# Sensor.net
KiCad netlist of a schematic drawn in Altium Designer
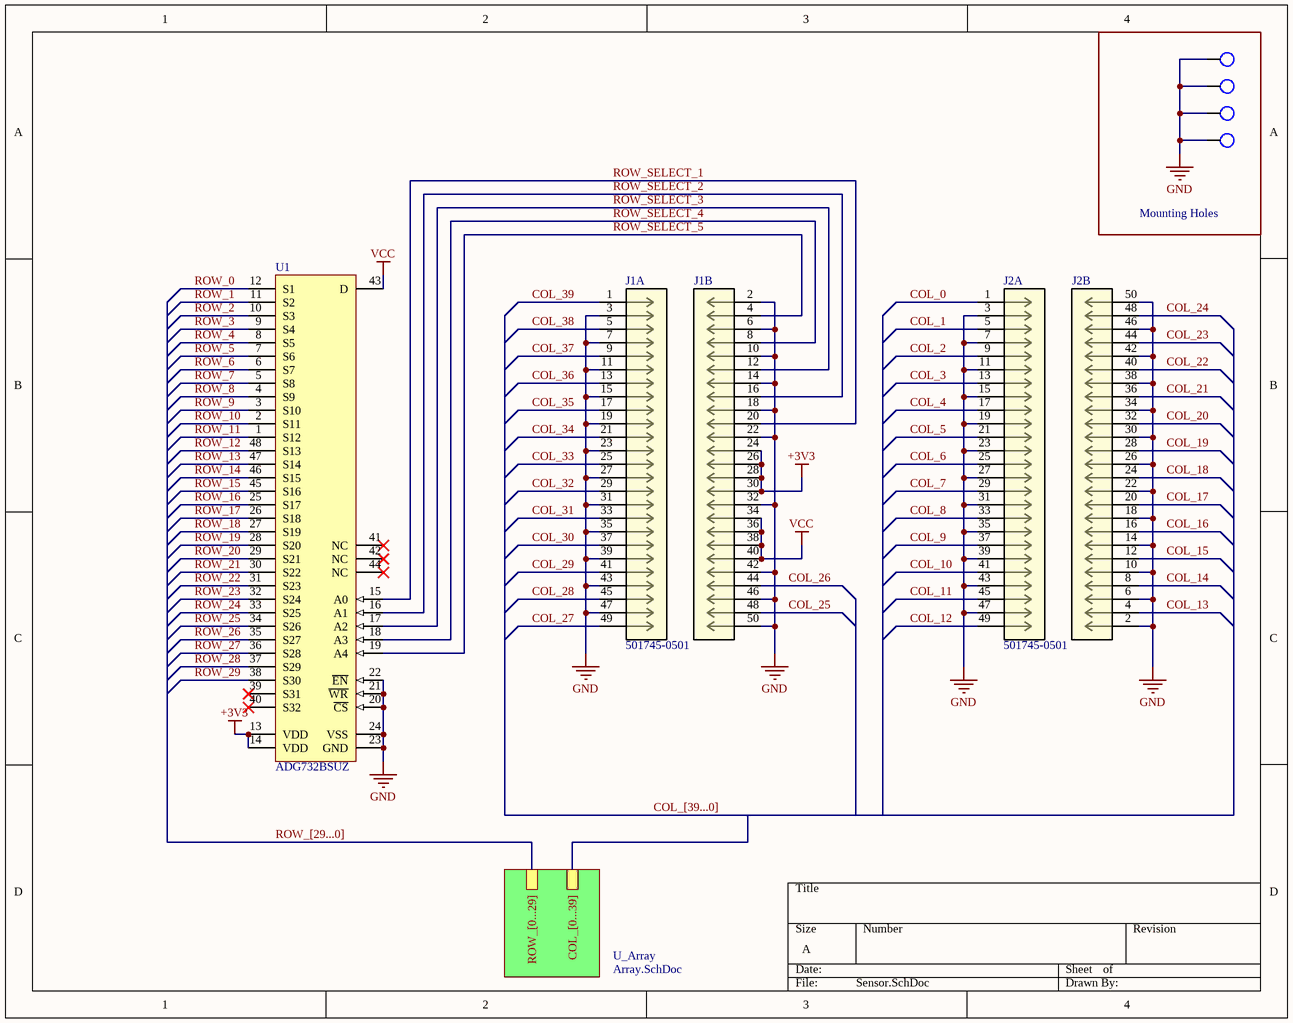
[diagram p0: Sensor.SchDoc]

(export (version "E")
  (design (tool "Eeschema 10.0.6"))
  (components
    (comp (ref "J1")
      (value "501745-0501")
      (footprint "501745-0501")
      (fields (field (name "MANUFACTURER") "Molex"))
      (libsource (lib "NeoObscura") (part "501745-0501"))
    )
    (comp (ref "J2")
      (value "501745-0501")
      (footprint "501745-0501")
      (fields (field (name "MANUFACTURER") "Molex"))
      (libsource (lib "NeoObscura") (part "501745-0501"))
    )
    (comp (ref "MP1")
      (value "M3 MOUNTING HOLE")
      (footprint "M3 MOUNTING HOLE")
      (libsource (lib "NeoObscura") (part "M3 MOUNTING HOLE"))
    )
    (comp (ref "MP2")
      (value "M3 MOUNTING HOLE")
      (footprint "M3 MOUNTING HOLE")
      (libsource (lib "NeoObscura") (part "M3 MOUNTING HOLE"))
    )
    (comp (ref "MP3")
      (value "M3 MOUNTING HOLE")
      (footprint "M3 MOUNTING HOLE")
      (libsource (lib "NeoObscura") (part "M3 MOUNTING HOLE"))
    )
    (comp (ref "MP4")
      (value "M3 MOUNTING HOLE")
      (footprint "M3 MOUNTING HOLE")
      (libsource (lib "NeoObscura") (part "M3 MOUNTING HOLE"))
    )
    (comp (ref "U1")
      (value "ADG732BSUZ")
      (footprint "ADI-SU-48_M")
      (fields (field (name "MANUFACTURER") "Analog Devices"))
      (libsource (lib "Altium Content Vault") (part "ADI-ADG732-SU-48"))
    )
  )
  (nets
    (net (code "3") (name "+3V3") (class "Default")
      (node (ref "J1") (pin "24") (pinfunction "24_24") (pintype "passive"))
      (node (ref "J1") (pin "26") (pinfunction "26_26") (pintype "passive"))
      (node (ref "J1") (pin "28") (pinfunction "28_28") (pintype "passive"))
      (node (ref "J1") (pin "30") (pinfunction "30_30") (pintype "passive"))
      (node (ref "U1") (pin "13") (pinfunction "VDD_13") (pintype "power_in"))
      (node (ref "U1") (pin "14") (pinfunction "VDD_14") (pintype "power_in"))
    )
    (net (code "4") (name "/COL_0") (class "Default")
      (node (ref "J2") (pin "1") (pinfunction "1_1") (pintype "passive"))
    )
    (net (code "5") (name "/COL_1") (class "Default")
      (node (ref "J2") (pin "5") (pinfunction "5_5") (pintype "passive"))
    )
    (net (code "6") (name "/COL_2") (class "Default")
      (node (ref "J2") (pin "9") (pinfunction "9_9") (pintype "passive"))
    )
    (net (code "7") (name "/COL_3") (class "Default")
      (node (ref "J2") (pin "13") (pinfunction "13_13") (pintype "passive"))
    )
    (net (code "8") (name "/COL_4") (class "Default")
      (node (ref "J2") (pin "17") (pinfunction "17_17") (pintype "passive"))
    )
    (net (code "9") (name "/COL_5") (class "Default")
      (node (ref "J2") (pin "21") (pinfunction "21_21") (pintype "passive"))
    )
    (net (code "10") (name "/COL_6") (class "Default")
      (node (ref "J2") (pin "25") (pinfunction "25_25") (pintype "passive"))
    )
    (net (code "11") (name "/COL_7") (class "Default")
      (node (ref "J2") (pin "29") (pinfunction "29_29") (pintype "passive"))
    )
    (net (code "12") (name "/COL_8") (class "Default")
      (node (ref "J2") (pin "33") (pinfunction "33_33") (pintype "passive"))
    )
    (net (code "13") (name "/COL_9") (class "Default")
      (node (ref "J2") (pin "37") (pinfunction "37_37") (pintype "passive"))
    )
    (net (code "14") (name "/COL_10") (class "Default")
      (node (ref "J2") (pin "41") (pinfunction "41_41") (pintype "passive"))
    )
    (net (code "15") (name "/COL_11") (class "Default")
      (node (ref "J2") (pin "45") (pinfunction "45_45") (pintype "passive"))
    )
    (net (code "16") (name "/COL_12") (class "Default")
      (node (ref "J2") (pin "49") (pinfunction "49_49") (pintype "passive"))
    )
    (net (code "17") (name "/COL_13") (class "Default")
      (node (ref "J2") (pin "4") (pinfunction "4_4") (pintype "passive"))
    )
    (net (code "18") (name "/COL_14") (class "Default")
      (node (ref "J2") (pin "8") (pinfunction "8_8") (pintype "passive"))
    )
    (net (code "19") (name "/COL_15") (class "Default")
      (node (ref "J2") (pin "12") (pinfunction "12_12") (pintype "passive"))
    )
    (net (code "20") (name "/COL_16") (class "Default")
      (node (ref "J2") (pin "16") (pinfunction "16_16") (pintype "passive"))
    )
    (net (code "21") (name "/COL_17") (class "Default")
      (node (ref "J2") (pin "20") (pinfunction "20_20") (pintype "passive"))
    )
    (net (code "22") (name "/COL_18") (class "Default")
      (node (ref "J2") (pin "24") (pinfunction "24_24") (pintype "passive"))
    )
    (net (code "23") (name "/COL_19") (class "Default")
      (node (ref "J2") (pin "28") (pinfunction "28_28") (pintype "passive"))
    )
    (net (code "24") (name "/COL_20") (class "Default")
      (node (ref "J2") (pin "32") (pinfunction "32_32") (pintype "passive"))
    )
    (net (code "25") (name "/COL_21") (class "Default")
      (node (ref "J2") (pin "36") (pinfunction "36_36") (pintype "passive"))
    )
    (net (code "26") (name "/COL_22") (class "Default")
      (node (ref "J2") (pin "40") (pinfunction "40_40") (pintype "passive"))
    )
    (net (code "27") (name "/COL_23") (class "Default")
      (node (ref "J2") (pin "44") (pinfunction "44_44") (pintype "passive"))
    )
    (net (code "28") (name "/COL_24") (class "Default")
      (node (ref "J2") (pin "48") (pinfunction "48_48") (pintype "passive"))
    )
    (net (code "29") (name "/COL_25") (class "Default")
      (node (ref "J1") (pin "48") (pinfunction "48_48") (pintype "passive"))
    )
    (net (code "30") (name "/COL_26") (class "Default")
      (node (ref "J1") (pin "44") (pinfunction "44_44") (pintype "passive"))
    )
    (net (code "31") (name "/COL_27") (class "Default")
      (node (ref "J1") (pin "49") (pinfunction "49_49") (pintype "passive"))
    )
    (net (code "32") (name "/COL_28") (class "Default")
      (node (ref "J1") (pin "45") (pinfunction "45_45") (pintype "passive"))
    )
    (net (code "33") (name "/COL_29") (class "Default")
      (node (ref "J1") (pin "41") (pinfunction "41_41") (pintype "passive"))
    )
    (net (code "34") (name "/COL_30") (class "Default")
      (node (ref "J1") (pin "37") (pinfunction "37_37") (pintype "passive"))
    )
    (net (code "35") (name "/COL_31") (class "Default")
      (node (ref "J1") (pin "33") (pinfunction "33_33") (pintype "passive"))
    )
    (net (code "36") (name "/COL_32") (class "Default")
      (node (ref "J1") (pin "29") (pinfunction "29_29") (pintype "passive"))
    )
    (net (code "37") (name "/COL_33") (class "Default")
      (node (ref "J1") (pin "25") (pinfunction "25_25") (pintype "passive"))
    )
    (net (code "38") (name "/COL_34") (class "Default")
      (node (ref "J1") (pin "21") (pinfunction "21_21") (pintype "passive"))
    )
    (net (code "39") (name "/COL_35") (class "Default")
      (node (ref "J1") (pin "17") (pinfunction "17_17") (pintype "passive"))
    )
    (net (code "40") (name "/COL_36") (class "Default")
      (node (ref "J1") (pin "13") (pinfunction "13_13") (pintype "passive"))
    )
    (net (code "41") (name "/COL_37") (class "Default")
      (node (ref "J1") (pin "9") (pinfunction "9_9") (pintype "passive"))
    )
    (net (code "42") (name "/COL_38") (class "Default")
      (node (ref "J1") (pin "5") (pinfunction "5_5") (pintype "passive"))
    )
    (net (code "43") (name "/COL_39") (class "Default")
      (node (ref "J1") (pin "1") (pinfunction "1_1") (pintype "passive"))
    )
    (net (code "44") (name "/ROW_0") (class "Default")
      (node (ref "U1") (pin "12") (pinfunction "S1_12") (pintype "passive"))
    )
    (net (code "45") (name "/ROW_1") (class "Default")
      (node (ref "U1") (pin "11") (pinfunction "S2_11") (pintype "passive"))
    )
    (net (code "46") (name "/ROW_2") (class "Default")
      (node (ref "U1") (pin "10") (pinfunction "S3_10") (pintype "passive"))
    )
    (net (code "47") (name "/ROW_3") (class "Default")
      (node (ref "U1") (pin "9") (pinfunction "S4_9") (pintype "passive"))
    )
    (net (code "48") (name "/ROW_4") (class "Default")
      (node (ref "U1") (pin "8") (pinfunction "S5_8") (pintype "passive"))
    )
    (net (code "49") (name "/ROW_5") (class "Default")
      (node (ref "U1") (pin "7") (pinfunction "S6_7") (pintype "passive"))
    )
    (net (code "50") (name "/ROW_6") (class "Default")
      (node (ref "U1") (pin "6") (pinfunction "S7_6") (pintype "passive"))
    )
    (net (code "51") (name "/ROW_7") (class "Default")
      (node (ref "U1") (pin "5") (pinfunction "S8_5") (pintype "passive"))
    )
    (net (code "52") (name "/ROW_8") (class "Default")
      (node (ref "U1") (pin "4") (pinfunction "S9_4") (pintype "passive"))
    )
    (net (code "53") (name "/ROW_9") (class "Default")
      (node (ref "U1") (pin "3") (pinfunction "S10_3") (pintype "passive"))
    )
    (net (code "54") (name "/ROW_10") (class "Default")
      (node (ref "U1") (pin "2") (pinfunction "S11_2") (pintype "passive"))
    )
    (net (code "55") (name "/ROW_11") (class "Default")
      (node (ref "U1") (pin "1") (pinfunction "S12_1") (pintype "passive"))
    )
    (net (code "56") (name "/ROW_12") (class "Default")
      (node (ref "U1") (pin "48") (pinfunction "S13_48") (pintype "passive"))
    )
    (net (code "57") (name "/ROW_13") (class "Default")
      (node (ref "U1") (pin "47") (pinfunction "S14_47") (pintype "passive"))
    )
    (net (code "58") (name "/ROW_14") (class "Default")
      (node (ref "U1") (pin "46") (pinfunction "S15_46") (pintype "passive"))
    )
    (net (code "59") (name "/ROW_15") (class "Default")
      (node (ref "U1") (pin "45") (pinfunction "S16_45") (pintype "passive"))
    )
    (net (code "60") (name "/ROW_16") (class "Default")
      (node (ref "U1") (pin "25") (pinfunction "S17_25") (pintype "passive"))
    )
    (net (code "61") (name "/ROW_17") (class "Default")
      (node (ref "U1") (pin "26") (pinfunction "S18_26") (pintype "passive"))
    )
    (net (code "62") (name "/ROW_18") (class "Default")
      (node (ref "U1") (pin "27") (pinfunction "S19_27") (pintype "passive"))
    )
    (net (code "63") (name "/ROW_19") (class "Default")
      (node (ref "U1") (pin "28") (pinfunction "S20_28") (pintype "passive"))
    )
    (net (code "64") (name "/ROW_20") (class "Default")
      (node (ref "U1") (pin "29") (pinfunction "S21_29") (pintype "passive"))
    )
    (net (code "65") (name "/ROW_21") (class "Default")
      (node (ref "U1") (pin "30") (pinfunction "S22_30") (pintype "passive"))
    )
    (net (code "66") (name "/ROW_22") (class "Default")
      (node (ref "U1") (pin "31") (pinfunction "S23_31") (pintype "passive"))
    )
    (net (code "67") (name "/ROW_23") (class "Default")
      (node (ref "U1") (pin "32") (pinfunction "S24_32") (pintype "passive"))
    )
    (net (code "68") (name "/ROW_24") (class "Default")
      (node (ref "U1") (pin "33") (pinfunction "S25_33") (pintype "passive"))
    )
    (net (code "69") (name "/ROW_25") (class "Default")
      (node (ref "U1") (pin "34") (pinfunction "S26_34") (pintype "passive"))
    )
    (net (code "70") (name "/ROW_26") (class "Default")
      (node (ref "U1") (pin "35") (pinfunction "S27_35") (pintype "passive"))
    )
    (net (code "71") (name "/ROW_27") (class "Default")
      (node (ref "U1") (pin "36") (pinfunction "S28_36") (pintype "passive"))
    )
    (net (code "72") (name "/ROW_28") (class "Default")
      (node (ref "U1") (pin "37") (pinfunction "S29_37") (pintype "passive"))
    )
    (net (code "73") (name "/ROW_29") (class "Default")
      (node (ref "U1") (pin "38") (pinfunction "S30_38") (pintype "passive"))
    )
    (net (code "74") (name "/ROW_SELECT_1") (class "Default")
      (node (ref "J1") (pin "20") (pinfunction "20_20") (pintype "passive"))
      (node (ref "U1") (pin "15") (pinfunction "A0_15") (pintype "input"))
    )
    (net (code "75") (name "/ROW_SELECT_2") (class "Default")
      (node (ref "J1") (pin "16") (pinfunction "16_16") (pintype "passive"))
      (node (ref "U1") (pin "16") (pinfunction "A1_16") (pintype "input"))
    )
    (net (code "76") (name "/ROW_SELECT_3") (class "Default")
      (node (ref "J1") (pin "12") (pinfunction "12_12") (pintype "passive"))
      (node (ref "U1") (pin "17") (pinfunction "A2_17") (pintype "input"))
    )
    (net (code "77") (name "/ROW_SELECT_4") (class "Default")
      (node (ref "J1") (pin "8") (pinfunction "8_8") (pintype "passive"))
      (node (ref "U1") (pin "18") (pinfunction "A3_18") (pintype "input"))
    )
    (net (code "78") (name "/ROW_SELECT_5") (class "Default")
      (node (ref "J1") (pin "4") (pinfunction "4_4") (pintype "passive"))
      (node (ref "U1") (pin "19") (pinfunction "A4_19") (pintype "input"))
    )
    (net (code "81") (name "GND") (class "Default")
      (node (ref "J1") (pin "10") (pinfunction "10_10") (pintype "passive"))
      (node (ref "J1") (pin "11") (pinfunction "11_11") (pintype "passive"))
      (node (ref "J1") (pin "14") (pinfunction "14_14") (pintype "passive"))
      (node (ref "J1") (pin "15") (pinfunction "15_15") (pintype "passive"))
      (node (ref "J1") (pin "18") (pinfunction "18_18") (pintype "passive"))
      (node (ref "J1") (pin "19") (pinfunction "19_19") (pintype "passive"))
      (node (ref "J1") (pin "2") (pinfunction "2_2") (pintype "passive"))
      (node (ref "J1") (pin "22") (pinfunction "22_22") (pintype "passive"))
      (node (ref "J1") (pin "23") (pinfunction "23_23") (pintype "passive"))
      (node (ref "J1") (pin "27") (pinfunction "27_27") (pintype "passive"))
      (node (ref "J1") (pin "3") (pinfunction "3_3") (pintype "passive"))
      (node (ref "J1") (pin "31") (pinfunction "31_31") (pintype "passive"))
      (node (ref "J1") (pin "32") (pinfunction "32_32") (pintype "passive"))
      (node (ref "J1") (pin "35") (pinfunction "35_35") (pintype "passive"))
      (node (ref "J1") (pin "39") (pinfunction "39_39") (pintype "passive"))
      (node (ref "J1") (pin "42") (pinfunction "42_42") (pintype "passive"))
      (node (ref "J1") (pin "43") (pinfunction "43_43") (pintype "passive"))
      (node (ref "J1") (pin "46") (pinfunction "46_46") (pintype "passive"))
      (node (ref "J1") (pin "47") (pinfunction "47_47") (pintype "passive"))
      (node (ref "J1") (pin "50") (pinfunction "50_50") (pintype "passive"))
      (node (ref "J1") (pin "6") (pinfunction "6_6") (pintype "passive"))
      (node (ref "J1") (pin "7") (pinfunction "7_7") (pintype "passive"))
      (node (ref "J2") (pin "10") (pinfunction "10_10") (pintype "passive"))
      (node (ref "J2") (pin "11") (pinfunction "11_11") (pintype "passive"))
      (node (ref "J2") (pin "14") (pinfunction "14_14") (pintype "passive"))
      (node (ref "J2") (pin "15") (pinfunction "15_15") (pintype "passive"))
      (node (ref "J2") (pin "18") (pinfunction "18_18") (pintype "passive"))
      (node (ref "J2") (pin "19") (pinfunction "19_19") (pintype "passive"))
      (node (ref "J2") (pin "2") (pinfunction "2_2") (pintype "passive"))
      (node (ref "J2") (pin "22") (pinfunction "22_22") (pintype "passive"))
      (node (ref "J2") (pin "23") (pinfunction "23_23") (pintype "passive"))
      (node (ref "J2") (pin "26") (pinfunction "26_26") (pintype "passive"))
      (node (ref "J2") (pin "27") (pinfunction "27_27") (pintype "passive"))
      (node (ref "J2") (pin "3") (pinfunction "3_3") (pintype "passive"))
      (node (ref "J2") (pin "30") (pinfunction "30_30") (pintype "passive"))
      (node (ref "J2") (pin "31") (pinfunction "31_31") (pintype "passive"))
      (node (ref "J2") (pin "34") (pinfunction "34_34") (pintype "passive"))
      (node (ref "J2") (pin "35") (pinfunction "35_35") (pintype "passive"))
      (node (ref "J2") (pin "38") (pinfunction "38_38") (pintype "passive"))
      (node (ref "J2") (pin "39") (pinfunction "39_39") (pintype "passive"))
      (node (ref "J2") (pin "42") (pinfunction "42_42") (pintype "passive"))
      (node (ref "J2") (pin "43") (pinfunction "43_43") (pintype "passive"))
      (node (ref "J2") (pin "46") (pinfunction "46_46") (pintype "passive"))
      (node (ref "J2") (pin "47") (pinfunction "47_47") (pintype "passive"))
      (node (ref "J2") (pin "50") (pinfunction "50_50") (pintype "passive"))
      (node (ref "J2") (pin "6") (pinfunction "6_6") (pintype "passive"))
      (node (ref "J2") (pin "7") (pinfunction "7_7") (pintype "passive"))
      (node (ref "MP1") (pin "1") (pinfunction "1_1") (pintype "passive"))
      (node (ref "MP2") (pin "1") (pinfunction "1_1") (pintype "passive"))
      (node (ref "MP3") (pin "1") (pinfunction "1_1") (pintype "passive"))
      (node (ref "MP4") (pin "1") (pinfunction "1_1") (pintype "passive"))
      (node (ref "U1") (pin "20") (pinfunction "~{CS}_20") (pintype "input"))
      (node (ref "U1") (pin "21") (pinfunction "~{WR}_21") (pintype "input"))
      (node (ref "U1") (pin "22") (pinfunction "~{EN}_22") (pintype "input"))
      (node (ref "U1") (pin "23") (pinfunction "GND_23") (pintype "power_in"))
      (node (ref "U1") (pin "24") (pinfunction "VSS_24") (pintype "power_in"))
    )
    (net (code "82") (name "VCC") (class "Default")
      (node (ref "J1") (pin "34") (pinfunction "34_34") (pintype "passive"))
      (node (ref "J1") (pin "36") (pinfunction "36_36") (pintype "passive"))
      (node (ref "J1") (pin "38") (pinfunction "38_38") (pintype "passive"))
      (node (ref "J1") (pin "40") (pinfunction "40_40") (pintype "passive"))
      (node (ref "U1") (pin "43") (pinfunction "D_43") (pintype "passive"))
    )
    (net (code "83") (name "unconnected-(U1-NC-Pad41)") (class "Default")
      (node (ref "U1") (pin "41") (pinfunction "NC_41") (pintype "passive+no_connect"))
    )
    (net (code "84") (name "unconnected-(U1-NC-Pad42)") (class "Default")
      (node (ref "U1") (pin "42") (pinfunction "NC_42") (pintype "passive+no_connect"))
    )
    (net (code "85") (name "unconnected-(U1-NC-Pad44)") (class "Default")
      (node (ref "U1") (pin "44") (pinfunction "NC_44") (pintype "passive+no_connect"))
    )
    (net (code "86") (name "unconnected-(U1-S31-Pad39)") (class "Default")
      (node (ref "U1") (pin "39") (pinfunction "S31_39") (pintype "passive+no_connect"))
    )
    (net (code "87") (name "unconnected-(U1-S32-Pad40)") (class "Default")
      (node (ref "U1") (pin "40") (pinfunction "S32_40") (pintype "passive+no_connect"))
    )
  )
)
